# uC.net
KiCad netlist of a schematic drawn in Altium Designer
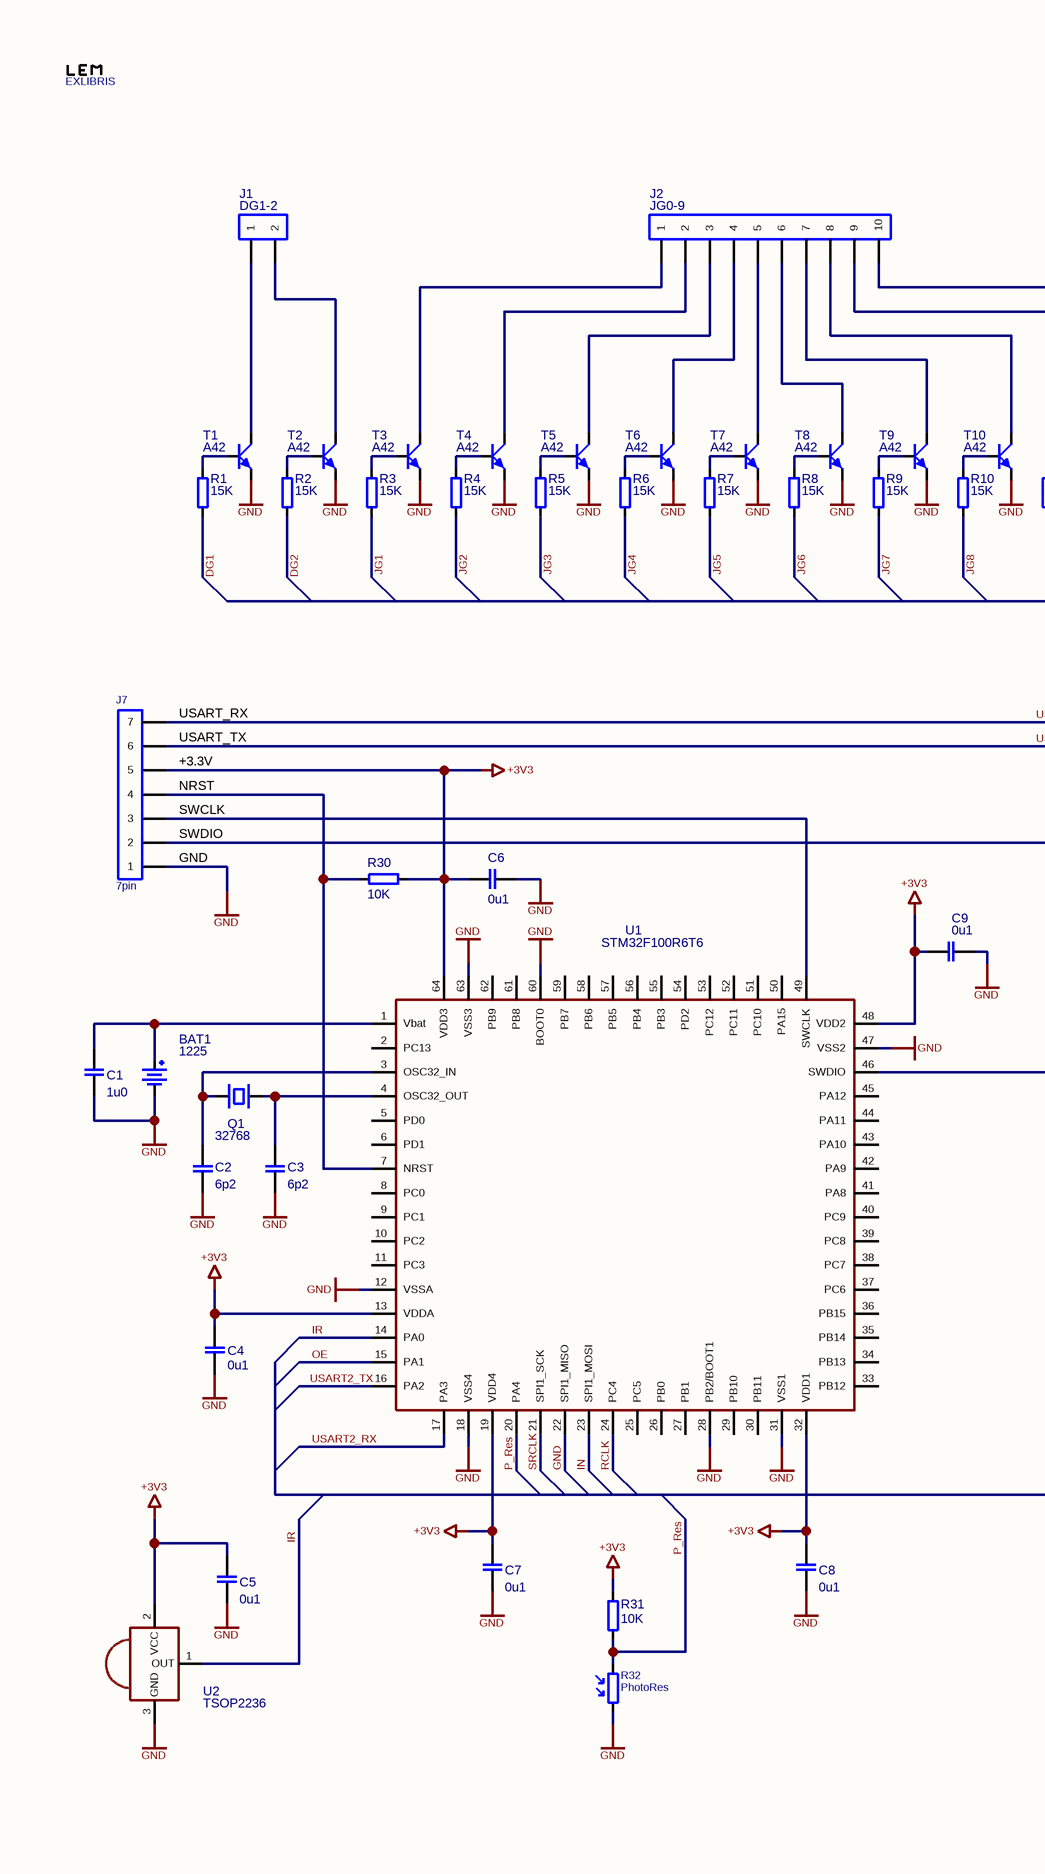
[diagram p0: uC.SchDoc, left]
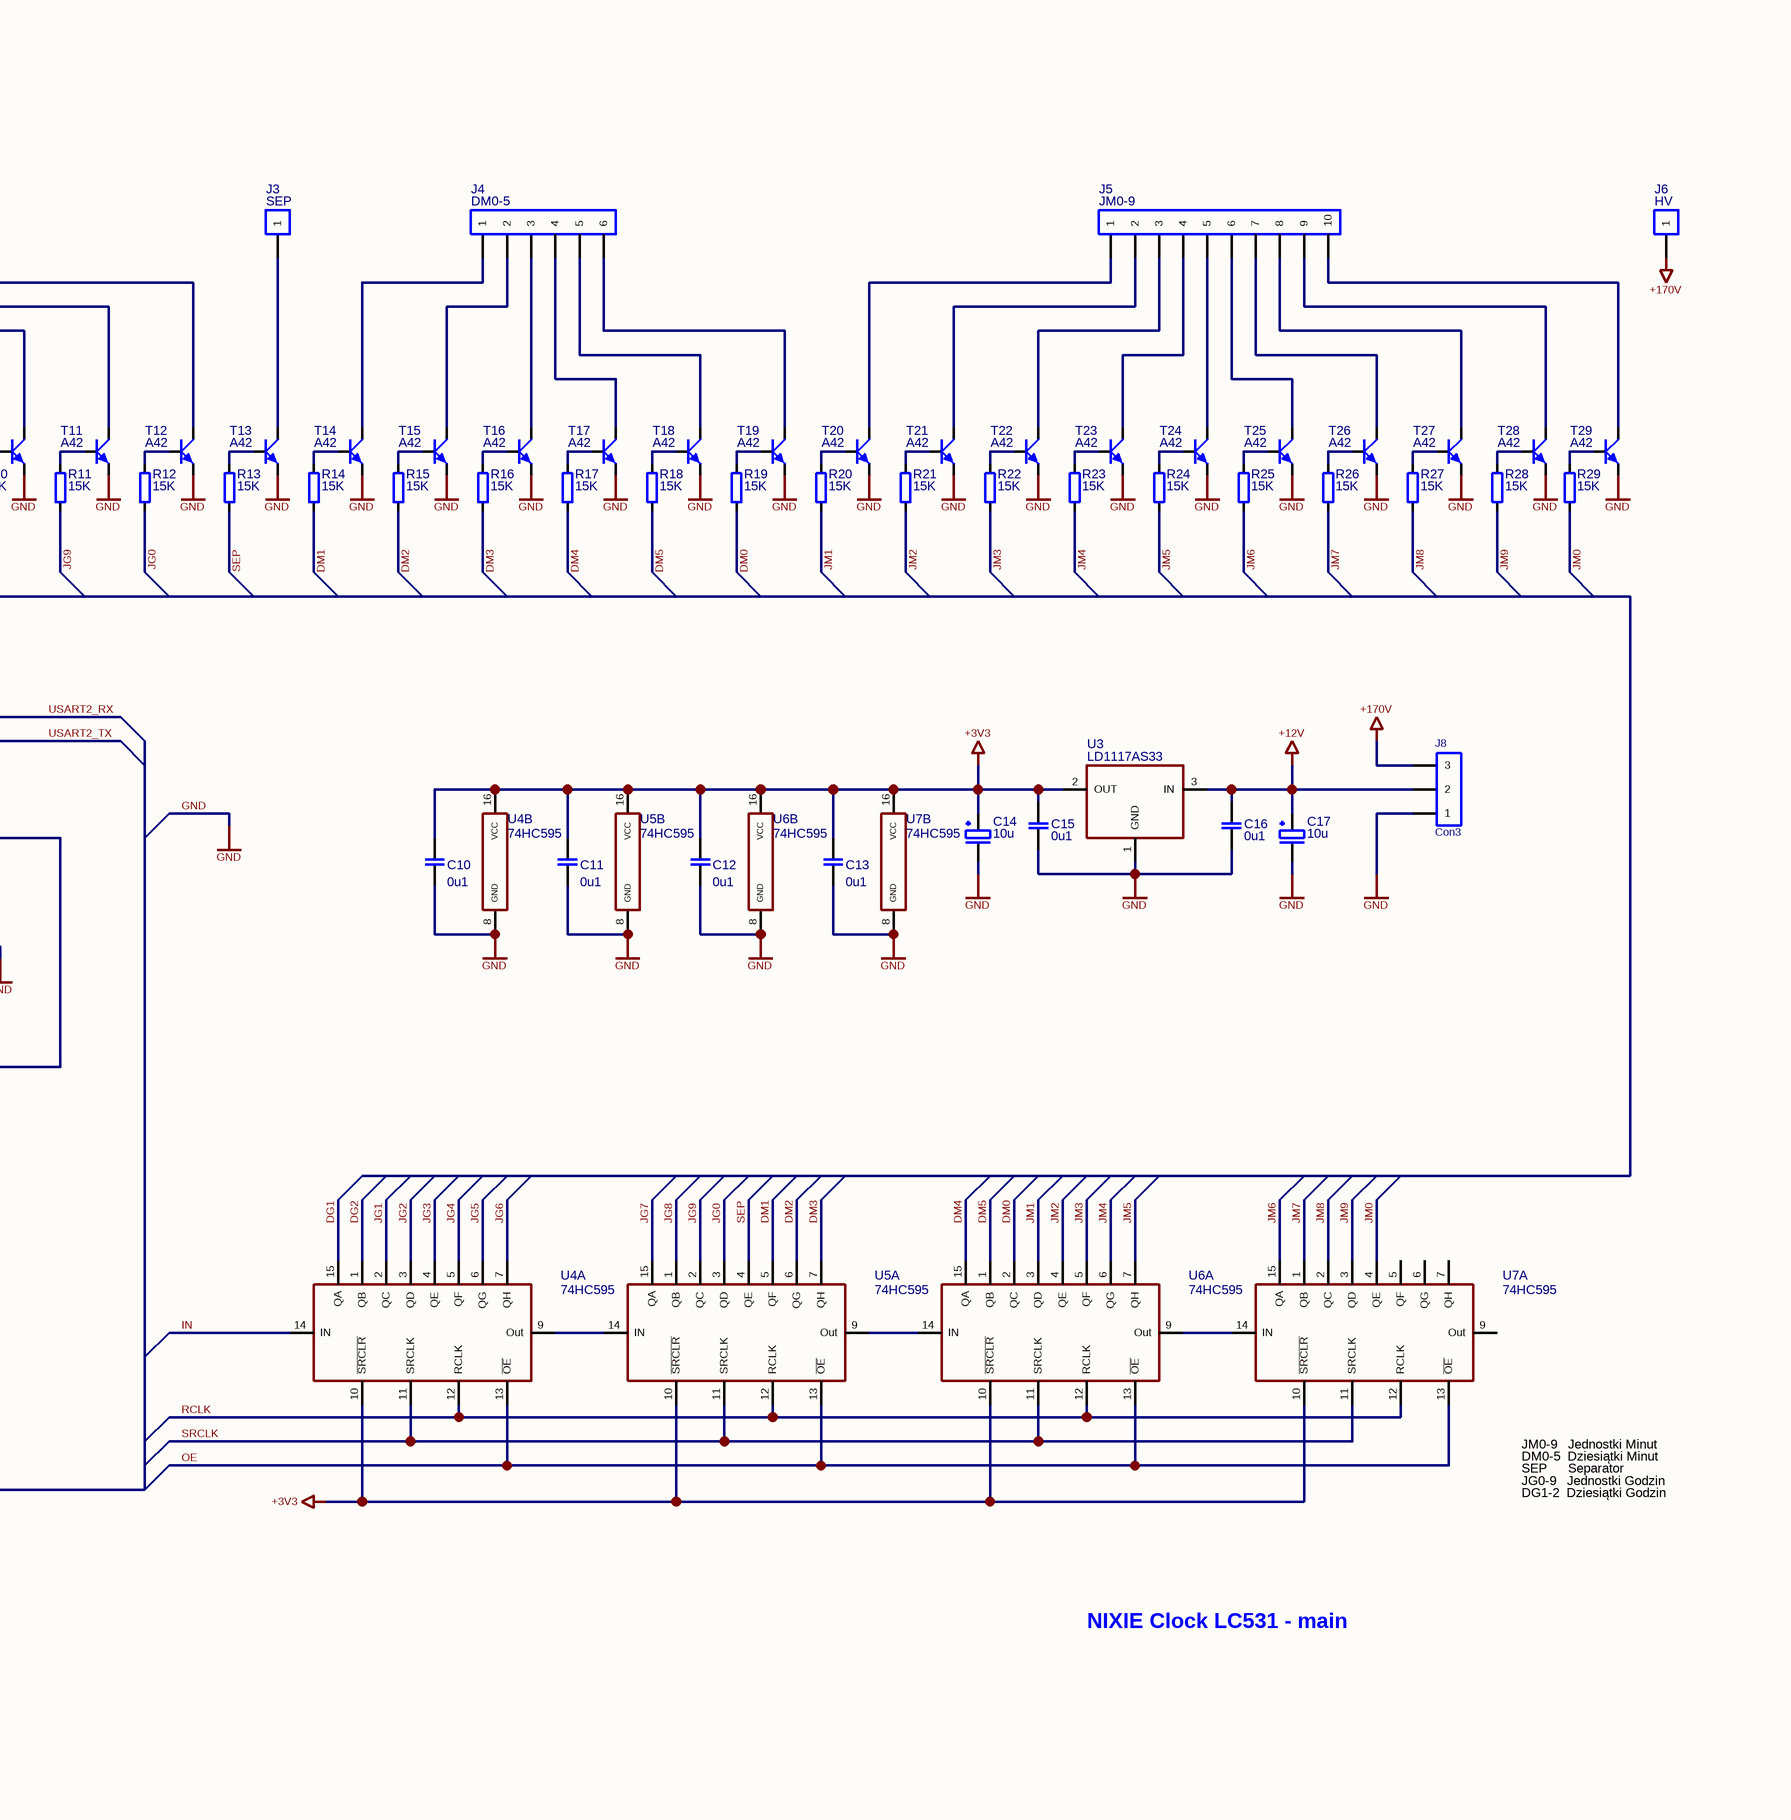
[diagram p1: uC.SchDoc, right]

(export (version "E")
  (design (tool "Eeschema 10.0.6"))
  (components
    (comp (ref "BAT1")
      (value "1225")
      (footprint "SMTU-1225")
      (description "Bateria Litowa 3V")
      (libsource (lib "Sch_Passive") (part "BAT_3V"))
    )
    (comp (ref "C1")
      (value "1u0")
      (footprint "C_SMD_0805")
      (description "Kondensator monolityczny")
      (libsource (lib "Caps") (part "C"))
    )
    (comp (ref "C2")
      (value "6p2")
      (footprint "C_SMD_0805")
      (description "Kondensator monolityczny")
      (libsource (lib "Caps") (part "C"))
    )
    (comp (ref "C3")
      (value "6p2")
      (footprint "C_SMD_0805")
      (description "Kondensator monolityczny")
      (libsource (lib "Caps") (part "C"))
    )
    (comp (ref "C4")
      (value "0u1")
      (footprint "C_SMD_0603")
      (description "Kondensator monolityczny")
      (libsource (lib "Caps") (part "C"))
    )
    (comp (ref "C5")
      (value "0u1")
      (footprint "C_SMD_0603")
      (description "Kondensator monolityczny")
      (libsource (lib "Caps") (part "C"))
    )
    (comp (ref "C6")
      (value "0u1")
      (footprint "C_SMD_0603")
      (description "Kondensator monolityczny")
      (libsource (lib "Caps") (part "C"))
    )
    (comp (ref "C7")
      (value "0u1")
      (footprint "C_SMD_0603")
      (description "Kondensator monolityczny")
      (libsource (lib "Caps") (part "C"))
    )
    (comp (ref "C8")
      (value "0u1")
      (footprint "C_SMD_0603")
      (description "Kondensator monolityczny")
      (libsource (lib "Caps") (part "C"))
    )
    (comp (ref "C9")
      (value "0u1")
      (footprint "C_SMD_0603")
      (description "Kondensator monolityczny")
      (libsource (lib "Caps") (part "C"))
    )
    (comp (ref "C10")
      (value "0u1")
      (footprint "C_SMD_0603")
      (description "Kondensator monolityczny")
      (libsource (lib "Caps") (part "C"))
    )
    (comp (ref "C11")
      (value "0u1")
      (footprint "C_SMD_0603")
      (description "Kondensator monolityczny")
      (libsource (lib "Caps") (part "C"))
    )
    (comp (ref "C12")
      (value "0u1")
      (footprint "C_SMD_0603")
      (description "Kondensator monolityczny")
      (libsource (lib "Caps") (part "C"))
    )
    (comp (ref "C13")
      (value "0u1")
      (footprint "C_SMD_0603")
      (description "Kondensator monolityczny")
      (libsource (lib "Caps") (part "C"))
    )
    (comp (ref "C14")
      (value "10u")
      (footprint "CE_T_SMC_6032_28")
      (description "Kondensator elektrolityczny")
      (libsource (lib "Caps") (part "CE"))
    )
    (comp (ref "C15")
      (value "0u1")
      (footprint "C_SMD_0603")
      (description "Kondensator monolityczny")
      (libsource (lib "Caps") (part "C"))
    )
    (comp (ref "C16")
      (value "0u1")
      (footprint "C_SMD_0603")
      (description "Kondensator monolityczny")
      (libsource (lib "Caps") (part "C"))
    )
    (comp (ref "C17")
      (value "10u")
      (footprint "CE_T_SMC_6032_28")
      (description "Kondensator elektrolityczny")
      (libsource (lib "Caps") (part "CE"))
    )
    (comp (ref "EXLIBRIS") (value "EXLIBRIS") (footprint "EXLBS_2") (libsource (lib "Misc") (part "EXLBR")))
    (comp (ref "J1")
      (value "DG1-2")
      (footprint "SIL2_GP_V")
      (description "Connector 2pin")
      (libsource (lib "Connectors") (part "CON 2pin"))
    )
    (comp (ref "J2")
      (value "JG0-9")
      (footprint "SIL10")
      (description "Connector 10 pin")
      (libsource (lib "Connectors") (part "CON 10pin"))
    )
    (comp (ref "J3")
      (value "SEP")
      (footprint "SIL1")
      (description "Connector 1pin also mounting hole")
      (libsource (lib "Connectors") (part "CON 1pin"))
    )
    (comp (ref "J4")
      (value "DM0-5")
      (footprint "SIL6_GP_V")
      (description "6 Pin Connector")
      (libsource (lib "Connectors") (part "CON 6pin"))
    )
    (comp (ref "J5")
      (value "JM0-9")
      (footprint "SIL10")
      (description "Connector 10 pin")
      (libsource (lib "Connectors") (part "CON 10pin"))
    )
    (comp (ref "J6")
      (value "HV")
      (footprint "SIL1")
      (description "Connector 1pin also mounting hole")
      (libsource (lib "Connectors") (part "CON 1pin"))
    )
    (comp (ref "J7")
      (value "7pin")
      (footprint "SIL7_SMD_Horizontal")
      (description "Connector 7pin")
      (libsource (lib "Connectors") (part "CON 7pin"))
    )
    (comp (ref "J8")
      (value "Con3")
      (footprint "TE_147323-2")
      (description "Connector 3pin")
      (libsource (lib "Connectors") (part "CON 3pin"))
    )
    (comp (ref "Q1")
      (value "32768")
      (footprint "XTAL_3")
      (description "Rezonator kwarcowy")
      (libsource (lib "Sch_Passive") (part "Q"))
    )
    (comp (ref "R1")
      (value "15K")
      (footprint "R_SMD_0603")
      (description "Resistor")
      (libsource (lib "Res") (part "R"))
    )
    (comp (ref "R2")
      (value "15K")
      (footprint "R_SMD_0603")
      (description "Resistor")
      (libsource (lib "Res") (part "R"))
    )
    (comp (ref "R3")
      (value "15K")
      (footprint "R_SMD_0603")
      (description "Resistor")
      (libsource (lib "Res") (part "R"))
    )
    (comp (ref "R4")
      (value "15K")
      (footprint "R_SMD_0603")
      (description "Resistor")
      (libsource (lib "Res") (part "R"))
    )
    (comp (ref "R5")
      (value "15K")
      (footprint "R_SMD_0603")
      (description "Resistor")
      (libsource (lib "Res") (part "R"))
    )
    (comp (ref "R6")
      (value "15K")
      (footprint "R_SMD_0603")
      (description "Resistor")
      (libsource (lib "Res") (part "R"))
    )
    (comp (ref "R7")
      (value "15K")
      (footprint "R_SMD_0603")
      (description "Resistor")
      (libsource (lib "Res") (part "R"))
    )
    (comp (ref "R8")
      (value "15K")
      (footprint "R_SMD_0603")
      (description "Resistor")
      (libsource (lib "Res") (part "R"))
    )
    (comp (ref "R9")
      (value "15K")
      (footprint "R_SMD_0603")
      (description "Resistor")
      (libsource (lib "Res") (part "R"))
    )
    (comp (ref "R10")
      (value "15K")
      (footprint "R_SMD_0603")
      (description "Resistor")
      (libsource (lib "Res") (part "R"))
    )
    (comp (ref "R11")
      (value "15K")
      (footprint "R_SMD_0603")
      (description "Resistor")
      (libsource (lib "Res") (part "R"))
    )
    (comp (ref "R12")
      (value "15K")
      (footprint "R_SMD_0603")
      (description "Resistor")
      (libsource (lib "Res") (part "R"))
    )
    (comp (ref "R13")
      (value "15K")
      (footprint "R_SMD_0603")
      (description "Resistor")
      (libsource (lib "Res") (part "R"))
    )
    (comp (ref "R14")
      (value "15K")
      (footprint "R_SMD_0603")
      (description "Resistor")
      (libsource (lib "Res") (part "R"))
    )
    (comp (ref "R15")
      (value "15K")
      (footprint "R_SMD_0603")
      (description "Resistor")
      (libsource (lib "Res") (part "R"))
    )
    (comp (ref "R16")
      (value "15K")
      (footprint "R_SMD_0603")
      (description "Resistor")
      (libsource (lib "Res") (part "R"))
    )
    (comp (ref "R17")
      (value "15K")
      (footprint "R_SMD_0603")
      (description "Resistor")
      (libsource (lib "Res") (part "R"))
    )
    (comp (ref "R18")
      (value "15K")
      (footprint "R_SMD_0603")
      (description "Resistor")
      (libsource (lib "Res") (part "R"))
    )
    (comp (ref "R19")
      (value "15K")
      (footprint "R_SMD_0603")
      (description "Resistor")
      (libsource (lib "Res") (part "R"))
    )
    (comp (ref "R20")
      (value "15K")
      (footprint "R_SMD_0603")
      (description "Resistor")
      (libsource (lib "Res") (part "R"))
    )
    (comp (ref "R21")
      (value "15K")
      (footprint "R_SMD_0603")
      (description "Resistor")
      (libsource (lib "Res") (part "R"))
    )
    (comp (ref "R22")
      (value "15K")
      (footprint "R_SMD_0603")
      (description "Resistor")
      (libsource (lib "Res") (part "R"))
    )
    (comp (ref "R23")
      (value "15K")
      (footprint "R_SMD_0603")
      (description "Resistor")
      (libsource (lib "Res") (part "R"))
    )
    (comp (ref "R24")
      (value "15K")
      (footprint "R_SMD_0603")
      (description "Resistor")
      (libsource (lib "Res") (part "R"))
    )
    (comp (ref "R25")
      (value "15K")
      (footprint "R_SMD_0603")
      (description "Resistor")
      (libsource (lib "Res") (part "R"))
    )
    (comp (ref "R26")
      (value "15K")
      (footprint "R_SMD_0603")
      (description "Resistor")
      (libsource (lib "Res") (part "R"))
    )
    (comp (ref "R27")
      (value "15K")
      (footprint "R_SMD_0603")
      (description "Resistor")
      (libsource (lib "Res") (part "R"))
    )
    (comp (ref "R28")
      (value "15K")
      (footprint "R_SMD_0603")
      (description "Resistor")
      (libsource (lib "Res") (part "R"))
    )
    (comp (ref "R29")
      (value "15K")
      (footprint "R_SMD_0603")
      (description "Resistor")
      (libsource (lib "Res") (part "R"))
    )
    (comp (ref "R30")
      (value "10K")
      (footprint "R_SMD_0603")
      (description "Resistor")
      (libsource (lib "Res") (part "R"))
    )
    (comp (ref "R31")
      (value "10K")
      (footprint "R_SMD_0603")
      (description "Resistor")
      (libsource (lib "Res") (part "R"))
    )
    (comp (ref "R32")
      (value "PhotoRes")
      (footprint "R_Photo_V")
      (description "Photo resistor")
      (libsource (lib "RLCDQ") (part "R_Ph"))
    )
    (comp (ref "T1")
      (value "A42")
      (footprint "SOT-23 - Basic")
      (description "High Voltage NPN transistor")
      (libsource (lib "Tranzystory") (part "MMBTA42"))
    )
    (comp (ref "T2")
      (value "A42")
      (footprint "SOT-23 - Basic")
      (description "High Voltage NPN transistor")
      (libsource (lib "Tranzystory") (part "MMBTA42"))
    )
    (comp (ref "T3")
      (value "A42")
      (footprint "SOT-23 - Basic")
      (description "High Voltage NPN transistor")
      (libsource (lib "Tranzystory") (part "MMBTA42"))
    )
    (comp (ref "T4")
      (value "A42")
      (footprint "SOT-23 - Basic")
      (description "High Voltage NPN transistor")
      (libsource (lib "Tranzystory") (part "MMBTA42"))
    )
    (comp (ref "T5")
      (value "A42")
      (footprint "SOT-23 - Basic")
      (description "High Voltage NPN transistor")
      (libsource (lib "Tranzystory") (part "MMBTA42"))
    )
    (comp (ref "T6")
      (value "A42")
      (footprint "SOT-23 - Basic")
      (description "High Voltage NPN transistor")
      (libsource (lib "Tranzystory") (part "MMBTA42"))
    )
    (comp (ref "T7")
      (value "A42")
      (footprint "SOT-23 - Basic")
      (description "High Voltage NPN transistor")
      (libsource (lib "Tranzystory") (part "MMBTA42"))
    )
    (comp (ref "T8")
      (value "A42")
      (footprint "SOT-23 - Basic")
      (description "High Voltage NPN transistor")
      (libsource (lib "Tranzystory") (part "MMBTA42"))
    )
    (comp (ref "T9")
      (value "A42")
      (footprint "SOT-23 - Basic")
      (description "High Voltage NPN transistor")
      (libsource (lib "Tranzystory") (part "MMBTA42"))
    )
    (comp (ref "T10")
      (value "A42")
      (footprint "SOT-23 - Basic")
      (description "High Voltage NPN transistor")
      (libsource (lib "Tranzystory") (part "MMBTA42"))
    )
    (comp (ref "T11")
      (value "A42")
      (footprint "SOT-23 - Basic")
      (description "High Voltage NPN transistor")
      (libsource (lib "Tranzystory") (part "MMBTA42"))
    )
    (comp (ref "T12")
      (value "A42")
      (footprint "SOT-23 - Basic")
      (description "High Voltage NPN transistor")
      (libsource (lib "Tranzystory") (part "MMBTA42"))
    )
    (comp (ref "T13")
      (value "A42")
      (footprint "SOT-23 - Basic")
      (description "High Voltage NPN transistor")
      (libsource (lib "Tranzystory") (part "MMBTA42"))
    )
    (comp (ref "T14")
      (value "A42")
      (footprint "SOT-23 - Basic")
      (description "High Voltage NPN transistor")
      (libsource (lib "Tranzystory") (part "MMBTA42"))
    )
    (comp (ref "T15")
      (value "A42")
      (footprint "SOT-23 - Basic")
      (description "High Voltage NPN transistor")
      (libsource (lib "Tranzystory") (part "MMBTA42"))
    )
    (comp (ref "T16")
      (value "A42")
      (footprint "SOT-23 - Basic")
      (description "High Voltage NPN transistor")
      (libsource (lib "Tranzystory") (part "MMBTA42"))
    )
    (comp (ref "T17")
      (value "A42")
      (footprint "SOT-23 - Basic")
      (description "High Voltage NPN transistor")
      (libsource (lib "Tranzystory") (part "MMBTA42"))
    )
    (comp (ref "T18")
      (value "A42")
      (footprint "SOT-23 - Basic")
      (description "High Voltage NPN transistor")
      (libsource (lib "Tranzystory") (part "MMBTA42"))
    )
    (comp (ref "T19")
      (value "A42")
      (footprint "SOT-23 - Basic")
      (description "High Voltage NPN transistor")
      (libsource (lib "Tranzystory") (part "MMBTA42"))
    )
    (comp (ref "T20")
      (value "A42")
      (footprint "SOT-23 - Basic")
      (description "High Voltage NPN transistor")
      (libsource (lib "Tranzystory") (part "MMBTA42"))
    )
    (comp (ref "T21")
      (value "A42")
      (footprint "SOT-23 - Basic")
      (description "High Voltage NPN transistor")
      (libsource (lib "Tranzystory") (part "MMBTA42"))
    )
    (comp (ref "T22")
      (value "A42")
      (footprint "SOT-23 - Basic")
      (description "High Voltage NPN transistor")
      (libsource (lib "Tranzystory") (part "MMBTA42"))
    )
    (comp (ref "T23")
      (value "A42")
      (footprint "SOT-23 - Basic")
      (description "High Voltage NPN transistor")
      (libsource (lib "Tranzystory") (part "MMBTA42"))
    )
    (comp (ref "T24")
      (value "A42")
      (footprint "SOT-23 - Basic")
      (description "High Voltage NPN transistor")
      (libsource (lib "Tranzystory") (part "MMBTA42"))
    )
    (comp (ref "T25")
      (value "A42")
      (footprint "SOT-23 - Basic")
      (description "High Voltage NPN transistor")
      (libsource (lib "Tranzystory") (part "MMBTA42"))
    )
    (comp (ref "T26")
      (value "A42")
      (footprint "SOT-23 - Basic")
      (description "High Voltage NPN transistor")
      (libsource (lib "Tranzystory") (part "MMBTA42"))
    )
    (comp (ref "T27")
      (value "A42")
      (footprint "SOT-23 - Basic")
      (description "High Voltage NPN transistor")
      (libsource (lib "Tranzystory") (part "MMBTA42"))
    )
    (comp (ref "T28")
      (value "A42")
      (footprint "SOT-23 - Basic")
      (description "High Voltage NPN transistor")
      (libsource (lib "Tranzystory") (part "MMBTA42"))
    )
    (comp (ref "T29")
      (value "A42")
      (footprint "SOT-23 - Basic")
      (description "High Voltage NPN transistor")
      (libsource (lib "Tranzystory") (part "MMBTA42"))
    )
    (comp (ref "U1")
      (value "STM32F100R6T6")
      (footprint "LQFP-674")
      (libsource (lib "uC") (part "STM32F100R6T6"))
    )
    (comp (ref "U2") (value "TSOP2236") (footprint "TSOP-2236") (libsource (lib "uC") (part "IR Reciver")))
    (comp (ref "U3") (value "LD1117AS33") (footprint "SOT-223") (libsource (lib "uC") (part "AMS1117_3V3")))
    (comp (ref "U4")
      (value "74HC595")
      (footprint "SO-16_150")
      (description "8-bit shift registers with 3-state output")
      (libsource (lib "uC") (part "74595"))
    )
    (comp (ref "U5")
      (value "74HC595")
      (footprint "SO-16_150")
      (description "8-bit shift registers with 3-state output")
      (libsource (lib "uC") (part "74595"))
    )
    (comp (ref "U6")
      (value "74HC595")
      (footprint "SO-16_150")
      (description "8-bit shift registers with 3-state output")
      (libsource (lib "uC") (part "74595"))
    )
    (comp (ref "U7")
      (value "74HC595")
      (footprint "SO-16_150")
      (description "8-bit shift registers with 3-state output")
      (libsource (lib "uC") (part "74595"))
    )
  )
  (nets
    (net (code "1") (name "+3V3") (class "Default")
      (node (ref "C10") (pin "2") (pinfunction "2_2") (pintype "passive"))
      (node (ref "C11") (pin "2") (pinfunction "2_2") (pintype "passive"))
      (node (ref "C12") (pin "2") (pinfunction "2_2") (pintype "passive"))
      (node (ref "C13") (pin "2") (pinfunction "2_2") (pintype "passive"))
      (node (ref "C14") (pin "2") (pinfunction "+_2") (pintype "passive"))
      (node (ref "C15") (pin "2") (pinfunction "2_2") (pintype "passive"))
      (node (ref "C4") (pin "1") (pinfunction "1_1") (pintype "passive"))
      (node (ref "C5") (pin "2") (pinfunction "2_2") (pintype "passive"))
      (node (ref "C6") (pin "2") (pinfunction "2_2") (pintype "passive"))
      (node (ref "C7") (pin "2") (pinfunction "2_2") (pintype "passive"))
      (node (ref "C8") (pin "2") (pinfunction "2_2") (pintype "passive"))
      (node (ref "C9") (pin "1") (pinfunction "1_1") (pintype "passive"))
      (node (ref "J7") (pin "5") (pinfunction "5_5") (pintype "passive"))
      (node (ref "R30") (pin "1") (pinfunction "1_1") (pintype "passive"))
      (node (ref "R31") (pin "1") (pinfunction "1_1") (pintype "passive"))
      (node (ref "U1") (pin "13") (pinfunction "VDDA_13") (pintype "passive"))
      (node (ref "U1") (pin "19") (pinfunction "VDD4_19") (pintype "passive"))
      (node (ref "U1") (pin "32") (pinfunction "VDD1_32") (pintype "passive"))
      (node (ref "U1") (pin "48") (pinfunction "VDD2_48") (pintype "passive"))
      (node (ref "U1") (pin "64") (pinfunction "VDD3_64") (pintype "passive"))
      (node (ref "U2") (pin "2") (pinfunction "VCC_2") (pintype "passive"))
      (node (ref "U3") (pin "2") (pinfunction "OUT_2") (pintype "passive"))
      (node (ref "U4") (pin "10") (pinfunction "~{SRCLR}_10") (pintype "passive"))
      (node (ref "U4") (pin "16") (pinfunction "VCC_16") (pintype "passive"))
      (node (ref "U5") (pin "10") (pinfunction "~{SRCLR}_10") (pintype "passive"))
      (node (ref "U5") (pin "16") (pinfunction "VCC_16") (pintype "passive"))
      (node (ref "U6") (pin "10") (pinfunction "~{SRCLR}_10") (pintype "passive"))
      (node (ref "U6") (pin "16") (pinfunction "VCC_16") (pintype "passive"))
      (node (ref "U7") (pin "10") (pinfunction "~{SRCLR}_10") (pintype "passive"))
      (node (ref "U7") (pin "16") (pinfunction "VCC_16") (pintype "passive"))
    )
    (net (code "2") (name "+12V") (class "Default")
      (node (ref "C16") (pin "2") (pinfunction "2_2") (pintype "passive"))
      (node (ref "C17") (pin "2") (pinfunction "+_2") (pintype "passive"))
      (node (ref "J8") (pin "2") (pinfunction "2_2") (pintype "passive"))
      (node (ref "U3") (pin "3") (pinfunction "IN_3") (pintype "passive"))
    )
    (net (code "3") (name "+170V") (class "Default")
      (node (ref "J6") (pin "1") (pinfunction "1_1") (pintype "passive"))
      (node (ref "J8") (pin "3") (pinfunction "3_3") (pintype "passive"))
    )
    (net (code "4") (name "/DG1") (class "Default")
      (node (ref "R1") (pin "1") (pinfunction "1_1") (pintype "passive"))
      (node (ref "U4") (pin "15") (pinfunction "QA_15") (pintype "passive"))
    )
    (net (code "5") (name "/DG2") (class "Default")
      (node (ref "R2") (pin "1") (pinfunction "1_1") (pintype "passive"))
      (node (ref "U4") (pin "1") (pinfunction "QB_1") (pintype "passive"))
    )
    (net (code "6") (name "/DM0") (class "Default")
      (node (ref "R19") (pin "1") (pinfunction "1_1") (pintype "passive"))
      (node (ref "U6") (pin "2") (pinfunction "QC_2") (pintype "passive"))
    )
    (net (code "7") (name "/DM1") (class "Default")
      (node (ref "R14") (pin "1") (pinfunction "1_1") (pintype "passive"))
      (node (ref "U5") (pin "5") (pinfunction "QF_5") (pintype "passive"))
    )
    (net (code "8") (name "/DM2") (class "Default")
      (node (ref "R15") (pin "1") (pinfunction "1_1") (pintype "passive"))
      (node (ref "U5") (pin "6") (pinfunction "QG_6") (pintype "passive"))
    )
    (net (code "9") (name "/DM3") (class "Default")
      (node (ref "R16") (pin "1") (pinfunction "1_1") (pintype "passive"))
      (node (ref "U5") (pin "7") (pinfunction "QH_7") (pintype "passive"))
    )
    (net (code "10") (name "/DM4") (class "Default")
      (node (ref "R17") (pin "1") (pinfunction "1_1") (pintype "passive"))
      (node (ref "U6") (pin "15") (pinfunction "QA_15") (pintype "passive"))
    )
    (net (code "11") (name "/DM5") (class "Default")
      (node (ref "R18") (pin "2") (pinfunction "2_2") (pintype "passive"))
      (node (ref "U6") (pin "1") (pinfunction "QB_1") (pintype "passive"))
    )
    (net (code "12") (name "/IN") (class "Default")
      (node (ref "U1") (pin "23") (pinfunction "SPI1_MOSI_23") (pintype "passive"))
      (node (ref "U4") (pin "14") (pinfunction "IN_14") (pintype "passive"))
    )
    (net (code "13") (name "/IR") (class "Default")
      (node (ref "U1") (pin "14") (pinfunction "PA0_14") (pintype "passive"))
      (node (ref "U2") (pin "1") (pinfunction "OUT_1") (pintype "passive"))
    )
    (net (code "14") (name "/JG0") (class "Default")
      (node (ref "R12") (pin "1") (pinfunction "1_1") (pintype "passive"))
      (node (ref "U5") (pin "3") (pinfunction "QD_3") (pintype "passive"))
    )
    (net (code "15") (name "/JG1") (class "Default")
      (node (ref "R3") (pin "2") (pinfunction "2_2") (pintype "passive"))
      (node (ref "U4") (pin "2") (pinfunction "QC_2") (pintype "passive"))
    )
    (net (code "16") (name "/JG2") (class "Default")
      (node (ref "R4") (pin "1") (pinfunction "1_1") (pintype "passive"))
      (node (ref "U4") (pin "3") (pinfunction "QD_3") (pintype "passive"))
    )
    (net (code "17") (name "/JG3") (class "Default")
      (node (ref "R5") (pin "1") (pinfunction "1_1") (pintype "passive"))
      (node (ref "U4") (pin "4") (pinfunction "QE_4") (pintype "passive"))
    )
    (net (code "18") (name "/JG4") (class "Default")
      (node (ref "R6") (pin "1") (pinfunction "1_1") (pintype "passive"))
      (node (ref "U4") (pin "5") (pinfunction "QF_5") (pintype "passive"))
    )
    (net (code "19") (name "/JG5") (class "Default")
      (node (ref "R7") (pin "1") (pinfunction "1_1") (pintype "passive"))
      (node (ref "U4") (pin "6") (pinfunction "QG_6") (pintype "passive"))
    )
    (net (code "20") (name "/JG6") (class "Default")
      (node (ref "R8") (pin "2") (pinfunction "2_2") (pintype "passive"))
      (node (ref "U4") (pin "7") (pinfunction "QH_7") (pintype "passive"))
    )
    (net (code "21") (name "/JG7") (class "Default")
      (node (ref "R9") (pin "1") (pinfunction "1_1") (pintype "passive"))
      (node (ref "U5") (pin "15") (pinfunction "QA_15") (pintype "passive"))
    )
    (net (code "22") (name "/JG8") (class "Default")
      (node (ref "R10") (pin "1") (pinfunction "1_1") (pintype "passive"))
      (node (ref "U5") (pin "1") (pinfunction "QB_1") (pintype "passive"))
    )
    (net (code "23") (name "/JG9") (class "Default")
      (node (ref "R11") (pin "1") (pinfunction "1_1") (pintype "passive"))
      (node (ref "U5") (pin "2") (pinfunction "QC_2") (pintype "passive"))
    )
    (net (code "24") (name "/JM0") (class "Default")
      (node (ref "R29") (pin "1") (pinfunction "1_1") (pintype "passive"))
      (node (ref "U7") (pin "4") (pinfunction "QE_4") (pintype "passive"))
    )
    (net (code "25") (name "/JM1") (class "Default")
      (node (ref "R20") (pin "1") (pinfunction "1_1") (pintype "passive"))
      (node (ref "U6") (pin "3") (pinfunction "QD_3") (pintype "passive"))
    )
    (net (code "26") (name "/JM2") (class "Default")
      (node (ref "R21") (pin "1") (pinfunction "1_1") (pintype "passive"))
      (node (ref "U6") (pin "4") (pinfunction "QE_4") (pintype "passive"))
    )
    (net (code "27") (name "/JM3") (class "Default")
      (node (ref "R22") (pin "1") (pinfunction "1_1") (pintype "passive"))
      (node (ref "U6") (pin "5") (pinfunction "QF_5") (pintype "passive"))
    )
    (net (code "28") (name "/JM4") (class "Default")
      (node (ref "R23") (pin "2") (pinfunction "2_2") (pintype "passive"))
      (node (ref "U6") (pin "6") (pinfunction "QG_6") (pintype "passive"))
    )
    (net (code "29") (name "/JM5") (class "Default")
      (node (ref "R24") (pin "1") (pinfunction "1_1") (pintype "passive"))
      (node (ref "U6") (pin "7") (pinfunction "QH_7") (pintype "passive"))
    )
    (net (code "30") (name "/JM6") (class "Default")
      (node (ref "R25") (pin "1") (pinfunction "1_1") (pintype "passive"))
      (node (ref "U7") (pin "15") (pinfunction "QA_15") (pintype "passive"))
    )
    (net (code "31") (name "/JM7") (class "Default")
      (node (ref "R26") (pin "1") (pinfunction "1_1") (pintype "passive"))
      (node (ref "U7") (pin "1") (pinfunction "QB_1") (pintype "passive"))
    )
    (net (code "32") (name "/JM8") (class "Default")
      (node (ref "R27") (pin "1") (pinfunction "1_1") (pintype "passive"))
      (node (ref "U7") (pin "2") (pinfunction "QC_2") (pintype "passive"))
    )
    (net (code "33") (name "/JM9") (class "Default")
      (node (ref "R28") (pin "2") (pinfunction "2_2") (pintype "passive"))
      (node (ref "U7") (pin "3") (pinfunction "QD_3") (pintype "passive"))
    )
    (net (code "34") (name "/OE") (class "Default")
      (node (ref "U1") (pin "15") (pinfunction "PA1_15") (pintype "passive"))
      (node (ref "U4") (pin "13") (pinfunction "~{OE}_13") (pintype "passive"))
      (node (ref "U5") (pin "13") (pinfunction "~{OE}_13") (pintype "passive"))
      (node (ref "U6") (pin "13") (pinfunction "~{OE}_13") (pintype "passive"))
      (node (ref "U7") (pin "13") (pinfunction "~{OE}_13") (pintype "passive"))
    )
    (net (code "35") (name "/P_Res") (class "Default")
      (node (ref "R31") (pin "2") (pinfunction "2_2") (pintype "passive"))
      (node (ref "R32") (pin "2") (pinfunction "+_2") (pintype "passive"))
      (node (ref "U1") (pin "20") (pinfunction "PA4_20") (pintype "passive"))
    )
    (net (code "36") (name "/RCLK") (class "Default")
      (node (ref "U1") (pin "24") (pinfunction "PC4_24") (pintype "passive"))
      (node (ref "U4") (pin "12") (pinfunction "RCLK_12") (pintype "passive"))
      (node (ref "U5") (pin "12") (pinfunction "RCLK_12") (pintype "passive"))
      (node (ref "U6") (pin "12") (pinfunction "RCLK_12") (pintype "passive"))
      (node (ref "U7") (pin "12") (pinfunction "RCLK_12") (pintype "passive"))
    )
    (net (code "37") (name "/SEP") (class "Default")
      (node (ref "R13") (pin "2") (pinfunction "2_2") (pintype "passive"))
      (node (ref "U5") (pin "4") (pinfunction "QE_4") (pintype "passive"))
    )
    (net (code "38") (name "/SRCLK") (class "Default")
      (node (ref "U1") (pin "21") (pinfunction "SPI1_SCK_21") (pintype "passive"))
      (node (ref "U4") (pin "11") (pinfunction "SRCLK_11") (pintype "passive"))
      (node (ref "U5") (pin "11") (pinfunction "SRCLK_11") (pintype "passive"))
      (node (ref "U6") (pin "11") (pinfunction "SRCLK_11") (pintype "passive"))
      (node (ref "U7") (pin "11") (pinfunction "SRCLK_11") (pintype "passive"))
    )
    (net (code "39") (name "/USART2_RX") (class "Default")
      (node (ref "J7") (pin "7") (pinfunction "7_7") (pintype "passive"))
      (node (ref "U1") (pin "17") (pinfunction "PA3_17") (pintype "passive"))
    )
    (net (code "40") (name "/USART2_TX") (class "Default")
      (node (ref "J7") (pin "6") (pinfunction "6_6") (pintype "passive"))
      (node (ref "U1") (pin "16") (pinfunction "PA2_16") (pintype "passive"))
    )
    (net (code "41") (name "GND") (class "Default")
      (node (ref "BAT1") (pin "2") (pinfunction "-_2") (pintype "passive"))
      (node (ref "C1") (pin "1") (pinfunction "1_1") (pintype "passive"))
      (node (ref "C10") (pin "1") (pinfunction "1_1") (pintype "passive"))
      (node (ref "C11") (pin "1") (pinfunction "1_1") (pintype "passive"))
      (node (ref "C12") (pin "1") (pinfunction "1_1") (pintype "passive"))
      (node (ref "C13") (pin "1") (pinfunction "1_1") (pintype "passive"))
      (node (ref "C14") (pin "1") (pinfunction "-_1") (pintype "passive"))
      (node (ref "C15") (pin "1") (pinfunction "1_1") (pintype "passive"))
      (node (ref "C16") (pin "1") (pinfunction "1_1") (pintype "passive"))
      (node (ref "C17") (pin "1") (pinfunction "-_1") (pintype "passive"))
      (node (ref "C2") (pin "1") (pinfunction "1_1") (pintype "passive"))
      (node (ref "C3") (pin "1") (pinfunction "1_1") (pintype "passive"))
      (node (ref "C4") (pin "2") (pinfunction "2_2") (pintype "passive"))
      (node (ref "C5") (pin "1") (pinfunction "1_1") (pintype "passive"))
      (node (ref "C6") (pin "1") (pinfunction "1_1") (pintype "passive"))
      (node (ref "C7") (pin "1") (pinfunction "1_1") (pintype "passive"))
      (node (ref "C8") (pin "1") (pinfunction "1_1") (pintype "passive"))
      (node (ref "C9") (pin "2") (pinfunction "2_2") (pintype "passive"))
      (node (ref "J7") (pin "1") (pinfunction "1_1") (pintype "passive"))
      (node (ref "J8") (pin "1") (pinfunction "1_1") (pintype "passive"))
      (node (ref "R32") (pin "1") (pinfunction "-_1") (pintype "passive"))
      (node (ref "T1") (pin "2") (pinfunction "Emitter_2") (pintype "passive"))
      (node (ref "T10") (pin "2") (pinfunction "Emitter_2") (pintype "passive"))
      (node (ref "T11") (pin "2") (pinfunction "Emitter_2") (pintype "passive"))
      (node (ref "T12") (pin "2") (pinfunction "Emitter_2") (pintype "passive"))
      (node (ref "T13") (pin "2") (pinfunction "Emitter_2") (pintype "passive"))
      (node (ref "T14") (pin "2") (pinfunction "Emitter_2") (pintype "passive"))
      (node (ref "T15") (pin "2") (pinfunction "Emitter_2") (pintype "passive"))
      (node (ref "T16") (pin "2") (pinfunction "Emitter_2") (pintype "passive"))
      (node (ref "T17") (pin "2") (pinfunction "Emitter_2") (pintype "passive"))
      (node (ref "T18") (pin "2") (pinfunction "Emitter_2") (pintype "passive"))
      (node (ref "T19") (pin "2") (pinfunction "Emitter_2") (pintype "passive"))
      (node (ref "T2") (pin "2") (pinfunction "Emitter_2") (pintype "passive"))
      (node (ref "T20") (pin "2") (pinfunction "Emitter_2") (pintype "passive"))
      (node (ref "T21") (pin "2") (pinfunction "Emitter_2") (pintype "passive"))
      (node (ref "T22") (pin "2") (pinfunction "Emitter_2") (pintype "passive"))
      (node (ref "T23") (pin "2") (pinfunction "Emitter_2") (pintype "passive"))
      (node (ref "T24") (pin "2") (pinfunction "Emitter_2") (pintype "passive"))
      (node (ref "T25") (pin "2") (pinfunction "Emitter_2") (pintype "passive"))
      (node (ref "T26") (pin "2") (pinfunction "Emitter_2") (pintype "passive"))
      (node (ref "T27") (pin "2") (pinfunction "Emitter_2") (pintype "passive"))
      (node (ref "T28") (pin "2") (pinfunction "Emitter_2") (pintype "passive"))
      (node (ref "T29") (pin "2") (pinfunction "Emitter_2") (pintype "passive"))
      (node (ref "T3") (pin "2") (pinfunction "Emitter_2") (pintype "passive"))
      (node (ref "T4") (pin "2") (pinfunction "Emitter_2") (pintype "passive"))
      (node (ref "T5") (pin "2") (pinfunction "Emitter_2") (pintype "passive"))
      (node (ref "T6") (pin "2") (pinfunction "Emitter_2") (pintype "passive"))
      (node (ref "T7") (pin "2") (pinfunction "Emitter_2") (pintype "passive"))
      (node (ref "T8") (pin "2") (pinfunction "Emitter_2") (pintype "passive"))
      (node (ref "T9") (pin "2") (pinfunction "Emitter_2") (pintype "passive"))
      (node (ref "U1") (pin "12") (pinfunction "VSSA_12") (pintype "passive"))
      (node (ref "U1") (pin "18") (pinfunction "VSS4_18") (pintype "passive"))
      (node (ref "U1") (pin "22") (pinfunction "SPI1_MISO_22") (pintype "passive"))
      (node (ref "U1") (pin "28") (pinfunction "PB2/BOOT1_28") (pintype "passive"))
      (node (ref "U1") (pin "31") (pinfunction "VSS1_31") (pintype "passive"))
      (node (ref "U1") (pin "47") (pinfunction "VSS2_47") (pintype "passive"))
      (node (ref "U1") (pin "60") (pinfunction "BOOT0_60") (pintype "passive"))
      (node (ref "U1") (pin "63") (pinfunction "VSS3_63") (pintype "passive"))
      (node (ref "U2") (pin "3") (pinfunction "GND_3") (pintype "passive"))
      (node (ref "U3") (pin "1") (pinfunction "GND_1") (pintype "passive"))
      (node (ref "U4") (pin "8") (pinfunction "GND_8") (pintype "power_in"))
      (node (ref "U5") (pin "8") (pinfunction "GND_8") (pintype "power_in"))
      (node (ref "U6") (pin "8") (pinfunction "GND_8") (pintype "power_in"))
      (node (ref "U7") (pin "8") (pinfunction "GND_8") (pintype "power_in"))
    )
    (net (code "42") (name "Net-(BAT1-+)") (class "Default")
      (node (ref "BAT1") (pin "1") (pinfunction "+_1") (pintype "passive"))
      (node (ref "C1") (pin "2") (pinfunction "2_2") (pintype "passive"))
      (node (ref "U1") (pin "1") (pinfunction "Vbat_1") (pintype "passive"))
    )
    (net (code "43") (name "Net-(T1-Base)") (class "Default")
      (node (ref "R1") (pin "2") (pinfunction "2_2") (pintype "passive"))
      (node (ref "T1") (pin "1") (pinfunction "Base_1") (pintype "passive"))
    )
    (net (code "44") (name "Net-(T1-Collector)") (class "Default")
      (node (ref "J1") (pin "1") (pinfunction "1_1") (pintype "passive"))
      (node (ref "T1") (pin "3") (pinfunction "Collector_3") (pintype "passive"))
    )
    (net (code "45") (name "Net-(T2-Base)") (class "Default")
      (node (ref "R2") (pin "2") (pinfunction "2_2") (pintype "passive"))
      (node (ref "T2") (pin "1") (pinfunction "Base_1") (pintype "passive"))
    )
    (net (code "46") (name "Net-(T2-Collector)") (class "Default")
      (node (ref "J1") (pin "2") (pinfunction "2_2") (pintype "passive"))
      (node (ref "T2") (pin "3") (pinfunction "Collector_3") (pintype "passive"))
    )
    (net (code "47") (name "Net-(T3-Base)") (class "Default")
      (node (ref "R3") (pin "1") (pinfunction "1_1") (pintype "passive"))
      (node (ref "T3") (pin "1") (pinfunction "Base_1") (pintype "passive"))
    )
    (net (code "48") (name "Net-(T3-Collector)") (class "Default")
      (node (ref "J2") (pin "1") (pinfunction "1_1") (pintype "passive"))
      (node (ref "T3") (pin "3") (pinfunction "Collector_3") (pintype "passive"))
    )
    (net (code "49") (name "Net-(T4-Base)") (class "Default")
      (node (ref "R4") (pin "2") (pinfunction "2_2") (pintype "passive"))
      (node (ref "T4") (pin "1") (pinfunction "Base_1") (pintype "passive"))
    )
    (net (code "50") (name "Net-(T4-Collector)") (class "Default")
      (node (ref "J2") (pin "2") (pinfunction "2_2") (pintype "passive"))
      (node (ref "T4") (pin "3") (pinfunction "Collector_3") (pintype "passive"))
    )
    (net (code "51") (name "Net-(T5-Base)") (class "Default")
      (node (ref "R5") (pin "2") (pinfunction "2_2") (pintype "passive"))
      (node (ref "T5") (pin "1") (pinfunction "Base_1") (pintype "passive"))
    )
    (net (code "52") (name "Net-(T5-Collector)") (class "Default")
      (node (ref "J2") (pin "3") (pinfunction "3_3") (pintype "passive"))
      (node (ref "T5") (pin "3") (pinfunction "Collector_3") (pintype "passive"))
    )
    (net (code "53") (name "Net-(T6-Base)") (class "Default")
      (node (ref "R6") (pin "2") (pinfunction "2_2") (pintype "passive"))
      (node (ref "T6") (pin "1") (pinfunction "Base_1") (pintype "passive"))
    )
    (net (code "54") (name "Net-(T6-Collector)") (class "Default")
      (node (ref "J2") (pin "4") (pinfunction "4_4") (pintype "passive"))
      (node (ref "T6") (pin "3") (pinfunction "Collector_3") (pintype "passive"))
    )
    (net (code "55") (name "Net-(T7-Base)") (class "Default")
      (node (ref "R7") (pin "2") (pinfunction "2_2") (pintype "passive"))
      (node (ref "T7") (pin "1") (pinfunction "Base_1") (pintype "passive"))
    )
    (net (code "56") (name "Net-(T7-Collector)") (class "Default")
      (node (ref "J2") (pin "5") (pinfunction "5_5") (pintype "passive"))
      (node (ref "T7") (pin "3") (pinfunction "Collector_3") (pintype "passive"))
    )
    (net (code "57") (name "Net-(T8-Base)") (class "Default")
      (node (ref "R8") (pin "1") (pinfunction "1_1") (pintype "passive"))
      (node (ref "T8") (pin "1") (pinfunction "Base_1") (pintype "passive"))
    )
    (net (code "58") (name "Net-(T8-Collector)") (class "Default")
      (node (ref "J2") (pin "6") (pinfunction "6_6") (pintype "passive"))
      (node (ref "T8") (pin "3") (pinfunction "Collector_3") (pintype "passive"))
    )
    (net (code "59") (name "Net-(T9-Base)") (class "Default")
      (node (ref "R9") (pin "2") (pinfunction "2_2") (pintype "passive"))
      (node (ref "T9") (pin "1") (pinfunction "Base_1") (pintype "passive"))
    )
    (net (code "60") (name "Net-(T9-Collector)") (class "Default")
      (node (ref "J2") (pin "7") (pinfunction "7_7") (pintype "passive"))
      (node (ref "T9") (pin "3") (pinfunction "Collector_3") (pintype "passive"))
    )
    (net (code "61") (name "Net-(T10-Base)") (class "Default")
      (node (ref "R10") (pin "2") (pinfunction "2_2") (pintype "passive"))
      (node (ref "T10") (pin "1") (pinfunction "Base_1") (pintype "passive"))
    )
    (net (code "62") (name "Net-(T10-Collector)") (class "Default")
      (node (ref "J2") (pin "8") (pinfunction "8_8") (pintype "passive"))
      (node (ref "T10") (pin "3") (pinfunction "Collector_3") (pintype "passive"))
    )
    (net (code "63") (name "Net-(T11-Base)") (class "Default")
      (node (ref "R11") (pin "2") (pinfunction "2_2") (pintype "passive"))
      (node (ref "T11") (pin "1") (pinfunction "Base_1") (pintype "passive"))
    )
    (net (code "64") (name "Net-(T11-Collector)") (class "Default")
      (node (ref "J2") (pin "9") (pinfunction "9_9") (pintype "passive"))
      (node (ref "T11") (pin "3") (pinfunction "Collector_3") (pintype "passive"))
    )
    (net (code "65") (name "Net-(T12-Base)") (class "Default")
      (node (ref "R12") (pin "2") (pinfunction "2_2") (pintype "passive"))
      (node (ref "T12") (pin "1") (pinfunction "Base_1") (pintype "passive"))
    )
    (net (code "66") (name "Net-(T12-Collector)") (class "Default")
      (node (ref "J2") (pin "10") (pinfunction "10_10") (pintype "passive"))
      (node (ref "T12") (pin "3") (pinfunction "Collector_3") (pintype "passive"))
    )
    (net (code "67") (name "Net-(T13-Base)") (class "Default")
      (node (ref "R13") (pin "1") (pinfunction "1_1") (pintype "passive"))
      (node (ref "T13") (pin "1") (pinfunction "Base_1") (pintype "passive"))
    )
    (net (code "68") (name "Net-(T13-Collector)") (class "Default")
      (node (ref "J3") (pin "1") (pinfunction "1_1") (pintype "passive"))
      (node (ref "T13") (pin "3") (pinfunction "Collector_3") (pintype "passive"))
    )
    (net (code "69") (name "Net-(T14-Base)") (class "Default")
      (node (ref "R14") (pin "2") (pinfunction "2_2") (pintype "passive"))
      (node (ref "T14") (pin "1") (pinfunction "Base_1") (pintype "passive"))
    )
    (net (code "70") (name "Net-(T14-Collector)") (class "Default")
      (node (ref "J4") (pin "1") (pinfunction "1_1") (pintype "passive"))
      (node (ref "T14") (pin "3") (pinfunction "Collector_3") (pintype "passive"))
    )
    (net (code "71") (name "Net-(T15-Base)") (class "Default")
      (node (ref "R15") (pin "2") (pinfunction "2_2") (pintype "passive"))
      (node (ref "T15") (pin "1") (pinfunction "Base_1") (pintype "passive"))
    )
    (net (code "72") (name "Net-(T15-Collector)") (class "Default")
      (node (ref "J4") (pin "2") (pinfunction "2_2") (pintype "passive"))
      (node (ref "T15") (pin "3") (pinfunction "Collector_3") (pintype "passive"))
    )
    (net (code "73") (name "Net-(T16-Base)") (class "Default")
      (node (ref "R16") (pin "2") (pinfunction "2_2") (pintype "passive"))
      (node (ref "T16") (pin "1") (pinfunction "Base_1") (pintype "passive"))
    )
    (net (code "74") (name "Net-(T16-Collector)") (class "Default")
      (node (ref "J4") (pin "3") (pinfunction "3_3") (pintype "passive"))
      (node (ref "T16") (pin "3") (pinfunction "Collector_3") (pintype "passive"))
    )
    (net (code "75") (name "Net-(T17-Base)") (class "Default")
      (node (ref "R17") (pin "2") (pinfunction "2_2") (pintype "passive"))
      (node (ref "T17") (pin "1") (pinfunction "Base_1") (pintype "passive"))
    )
    (net (code "76") (name "Net-(T17-Collector)") (class "Default")
      (node (ref "J4") (pin "4") (pinfunction "4_4") (pintype "passive"))
      (node (ref "T17") (pin "3") (pinfunction "Collector_3") (pintype "passive"))
    )
    (net (code "77") (name "Net-(T18-Base)") (class "Default")
      (node (ref "R18") (pin "1") (pinfunction "1_1") (pintype "passive"))
      (node (ref "T18") (pin "1") (pinfunction "Base_1") (pintype "passive"))
    )
    (net (code "78") (name "Net-(T18-Collector)") (class "Default")
      (node (ref "J4") (pin "5") (pinfunction "5_5") (pintype "passive"))
      (node (ref "T18") (pin "3") (pinfunction "Collector_3") (pintype "passive"))
    )
    (net (code "79") (name "Net-(T19-Base)") (class "Default")
      (node (ref "R19") (pin "2") (pinfunction "2_2") (pintype "passive"))
      (node (ref "T19") (pin "1") (pinfunction "Base_1") (pintype "passive"))
    )
    (net (code "80") (name "Net-(T19-Collector)") (class "Default")
      (node (ref "J4") (pin "6") (pinfunction "6_6") (pintype "passive"))
      (node (ref "T19") (pin "3") (pinfunction "Collector_3") (pintype "passive"))
    )
    (net (code "81") (name "Net-(T20-Base)") (class "Default")
      (node (ref "R20") (pin "2") (pinfunction "2_2") (pintype "passive"))
      (node (ref "T20") (pin "1") (pinfunction "Base_1") (pintype "passive"))
    )
    (net (code "82") (name "Net-(T20-Collector)") (class "Default")
      (node (ref "J5") (pin "1") (pinfunction "1_1") (pintype "passive"))
      (node (ref "T20") (pin "3") (pinfunction "Collector_3") (pintype "passive"))
    )
    (net (code "83") (name "Net-(T21-Base)") (class "Default")
      (node (ref "R21") (pin "2") (pinfunction "2_2") (pintype "passive"))
      (node (ref "T21") (pin "1") (pinfunction "Base_1") (pintype "passive"))
    )
    (net (code "84") (name "Net-(T21-Collector)") (class "Default")
      (node (ref "J5") (pin "2") (pinfunction "2_2") (pintype "passive"))
      (node (ref "T21") (pin "3") (pinfunction "Collector_3") (pintype "passive"))
    )
    (net (code "85") (name "Net-(T22-Base)") (class "Default")
      (node (ref "R22") (pin "2") (pinfunction "2_2") (pintype "passive"))
      (node (ref "T22") (pin "1") (pinfunction "Base_1") (pintype "passive"))
    )
    (net (code "86") (name "Net-(T22-Collector)") (class "Default")
      (node (ref "J5") (pin "3") (pinfunction "3_3") (pintype "passive"))
      (node (ref "T22") (pin "3") (pinfunction "Collector_3") (pintype "passive"))
    )
    (net (code "87") (name "Net-(T23-Base)") (class "Default")
      (node (ref "R23") (pin "1") (pinfunction "1_1") (pintype "passive"))
      (node (ref "T23") (pin "1") (pinfunction "Base_1") (pintype "passive"))
    )
    (net (code "88") (name "Net-(T23-Collector)") (class "Default")
      (node (ref "J5") (pin "4") (pinfunction "4_4") (pintype "passive"))
      (node (ref "T23") (pin "3") (pinfunction "Collector_3") (pintype "passive"))
    )
    (net (code "89") (name "Net-(T24-Base)") (class "Default")
      (node (ref "R24") (pin "2") (pinfunction "2_2") (pintype "passive"))
      (node (ref "T24") (pin "1") (pinfunction "Base_1") (pintype "passive"))
    )
    (net (code "90") (name "Net-(T24-Collector)") (class "Default")
      (node (ref "J5") (pin "5") (pinfunction "5_5") (pintype "passive"))
      (node (ref "T24") (pin "3") (pinfunction "Collector_3") (pintype "passive"))
    )
    (net (code "91") (name "Net-(T25-Base)") (class "Default")
      (node (ref "R25") (pin "2") (pinfunction "2_2") (pintype "passive"))
      (node (ref "T25") (pin "1") (pinfunction "Base_1") (pintype "passive"))
    )
    (net (code "92") (name "Net-(T25-Collector)") (class "Default")
      (node (ref "J5") (pin "6") (pinfunction "6_6") (pintype "passive"))
      (node (ref "T25") (pin "3") (pinfunction "Collector_3") (pintype "passive"))
    )
    (net (code "93") (name "Net-(T26-Base)") (class "Default")
      (node (ref "R26") (pin "2") (pinfunction "2_2") (pintype "passive"))
      (node (ref "T26") (pin "1") (pinfunction "Base_1") (pintype "passive"))
    )
    (net (code "94") (name "Net-(T26-Collector)") (class "Default")
      (node (ref "J5") (pin "7") (pinfunction "7_7") (pintype "passive"))
      (node (ref "T26") (pin "3") (pinfunction "Collector_3") (pintype "passive"))
    )
    (net (code "95") (name "Net-(T27-Base)") (class "Default")
      (node (ref "R27") (pin "2") (pinfunction "2_2") (pintype "passive"))
      (node (ref "T27") (pin "1") (pinfunction "Base_1") (pintype "passive"))
    )
    (net (code "96") (name "Net-(T27-Collector)") (class "Default")
      (node (ref "J5") (pin "8") (pinfunction "8_8") (pintype "passive"))
      (node (ref "T27") (pin "3") (pinfunction "Collector_3") (pintype "passive"))
    )
    (net (code "97") (name "Net-(T28-Base)") (class "Default")
      (node (ref "R28") (pin "1") (pinfunction "1_1") (pintype "passive"))
      (node (ref "T28") (pin "1") (pinfunction "Base_1") (pintype "passive"))
    )
    (net (code "98") (name "Net-(T28-Collector)") (class "Default")
      (node (ref "J5") (pin "9") (pinfunction "9_9") (pintype "passive"))
      (node (ref "T28") (pin "3") (pinfunction "Collector_3") (pintype "passive"))
    )
    (net (code "99") (name "Net-(T29-Base)") (class "Default")
      (node (ref "R29") (pin "2") (pinfunction "2_2") (pintype "passive"))
      (node (ref "T29") (pin "1") (pinfunction "Base_1") (pintype "passive"))
    )
    (net (code "100") (name "Net-(T29-Collector)") (class "Default")
      (node (ref "J5") (pin "10") (pinfunction "10_10") (pintype "passive"))
      (node (ref "T29") (pin "3") (pinfunction "Collector_3") (pintype "passive"))
    )
    (net (code "101") (name "Net-(U1-NRST)") (class "Default")
      (node (ref "J7") (pin "4") (pinfunction "4_4") (pintype "passive"))
      (node (ref "R30") (pin "2") (pinfunction "2_2") (pintype "passive"))
      (node (ref "U1") (pin "7") (pinfunction "NRST_7") (pintype "passive"))
    )
    (net (code "102") (name "Net-(U1-OSC32_IN)") (class "Default")
      (node (ref "C2") (pin "2") (pinfunction "2_2") (pintype "passive"))
      (node (ref "Q1") (pin "1") (pinfunction "1_1") (pintype "passive"))
      (node (ref "U1") (pin "3") (pinfunction "OSC32_IN_3") (pintype "passive"))
    )
    (net (code "103") (name "Net-(U1-OSC32_OUT)") (class "Default")
      (node (ref "C3") (pin "2") (pinfunction "2_2") (pintype "passive"))
      (node (ref "Q1") (pin "2") (pinfunction "2_2") (pintype "passive"))
      (node (ref "U1") (pin "4") (pinfunction "OSC32_OUT_4") (pintype "passive"))
    )
    (net (code "104") (name "Net-(U1-SWCLK)") (class "Default")
      (node (ref "J7") (pin "3") (pinfunction "3_3") (pintype "passive"))
      (node (ref "U1") (pin "49") (pinfunction "SWCLK_49") (pintype "passive"))
    )
    (net (code "105") (name "Net-(U1-SWDIO)") (class "Default")
      (node (ref "J7") (pin "2") (pinfunction "2_2") (pintype "passive"))
      (node (ref "U1") (pin "46") (pinfunction "SWDIO_46") (pintype "passive"))
    )
    (net (code "106") (name "Net-(U4A-Out)") (class "Default")
      (node (ref "U4") (pin "9") (pinfunction "Out_9") (pintype "passive"))
      (node (ref "U5") (pin "14") (pinfunction "IN_14") (pintype "passive"))
    )
    (net (code "107") (name "Net-(U5A-Out)") (class "Default")
      (node (ref "U5") (pin "9") (pinfunction "Out_9") (pintype "passive"))
      (node (ref "U6") (pin "14") (pinfunction "IN_14") (pintype "passive"))
    )
    (net (code "108") (name "Net-(U6A-Out)") (class "Default")
      (node (ref "U6") (pin "9") (pinfunction "Out_9") (pintype "passive"))
      (node (ref "U7") (pin "14") (pinfunction "IN_14") (pintype "passive"))
    )
    (net (code "109") (name "unconnected-(U1-PA8-Pad41)") (class "Default")
      (node (ref "U1") (pin "41") (pinfunction "PA8_41") (pintype "passive"))
    )
    (net (code "110") (name "unconnected-(U1-PA9-Pad42)") (class "Default")
      (node (ref "U1") (pin "42") (pinfunction "PA9_42") (pintype "passive"))
    )
    (net (code "111") (name "unconnected-(U1-PA10-Pad43)") (class "Default")
      (node (ref "U1") (pin "43") (pinfunction "PA10_43") (pintype "passive"))
    )
    (net (code "112") (name "unconnected-(U1-PA11-Pad44)") (class "Default")
      (node (ref "U1") (pin "44") (pinfunction "PA11_44") (pintype "passive"))
    )
    (net (code "113") (name "unconnected-(U1-PA12-Pad45)") (class "Default")
      (node (ref "U1") (pin "45") (pinfunction "PA12_45") (pintype "passive"))
    )
    (net (code "114") (name "unconnected-(U1-PA15-Pad50)") (class "Default")
      (node (ref "U1") (pin "50") (pinfunction "PA15_50") (pintype "passive"))
    )
    (net (code "115") (name "unconnected-(U1-PB0-Pad26)") (class "Default")
      (node (ref "U1") (pin "26") (pinfunction "PB0_26") (pintype "passive"))
    )
    (net (code "116") (name "unconnected-(U1-PB1-Pad27)") (class "Default")
      (node (ref "U1") (pin "27") (pinfunction "PB1_27") (pintype "passive"))
    )
    (net (code "117") (name "unconnected-(U1-PB3-Pad55)") (class "Default")
      (node (ref "U1") (pin "55") (pinfunction "PB3_55") (pintype "passive"))
    )
    (net (code "118") (name "unconnected-(U1-PB4-Pad56)") (class "Default")
      (node (ref "U1") (pin "56") (pinfunction "PB4_56") (pintype "passive"))
    )
    (net (code "119") (name "unconnected-(U1-PB5-Pad57)") (class "Default")
      (node (ref "U1") (pin "57") (pinfunction "PB5_57") (pintype "passive"))
    )
    (net (code "120") (name "unconnected-(U1-PB6-Pad58)") (class "Default")
      (node (ref "U1") (pin "58") (pinfunction "PB6_58") (pintype "passive"))
    )
    (net (code "121") (name "unconnected-(U1-PB7-Pad59)") (class "Default")
      (node (ref "U1") (pin "59") (pinfunction "PB7_59") (pintype "passive"))
    )
    (net (code "122") (name "unconnected-(U1-PB8-Pad61)") (class "Default")
      (node (ref "U1") (pin "61") (pinfunction "PB8_61") (pintype "passive"))
    )
    (net (code "123") (name "unconnected-(U1-PB9-Pad62)") (class "Default")
      (node (ref "U1") (pin "62") (pinfunction "PB9_62") (pintype "passive"))
    )
    (net (code "124") (name "unconnected-(U1-PB10-Pad29)") (class "Default")
      (node (ref "U1") (pin "29") (pinfunction "PB10_29") (pintype "passive"))
    )
    (net (code "125") (name "unconnected-(U1-PB11-Pad30)") (class "Default")
      (node (ref "U1") (pin "30") (pinfunction "PB11_30") (pintype "passive"))
    )
    (net (code "126") (name "unconnected-(U1-PB12-Pad33)") (class "Default")
      (node (ref "U1") (pin "33") (pinfunction "PB12_33") (pintype "passive"))
    )
    (net (code "127") (name "unconnected-(U1-PB13-Pad34)") (class "Default")
      (node (ref "U1") (pin "34") (pinfunction "PB13_34") (pintype "passive"))
    )
    (net (code "128") (name "unconnected-(U1-PB14-Pad35)") (class "Default")
      (node (ref "U1") (pin "35") (pinfunction "PB14_35") (pintype "passive"))
    )
    (net (code "129") (name "unconnected-(U1-PB15-Pad36)") (class "Default")
      (node (ref "U1") (pin "36") (pinfunction "PB15_36") (pintype "passive"))
    )
    (net (code "130") (name "unconnected-(U1-PC0-Pad8)") (class "Default")
      (node (ref "U1") (pin "8") (pinfunction "PC0_8") (pintype "passive"))
    )
    (net (code "131") (name "unconnected-(U1-PC1-Pad9)") (class "Default")
      (node (ref "U1") (pin "9") (pinfunction "PC1_9") (pintype "passive"))
    )
    (net (code "132") (name "unconnected-(U1-PC2-Pad10)") (class "Default")
      (node (ref "U1") (pin "10") (pinfunction "PC2_10") (pintype "passive"))
    )
    (net (code "133") (name "unconnected-(U1-PC3-Pad11)") (class "Default")
      (node (ref "U1") (pin "11") (pinfunction "PC3_11") (pintype "passive"))
    )
    (net (code "134") (name "unconnected-(U1-PC5-Pad25)") (class "Default")
      (node (ref "U1") (pin "25") (pinfunction "PC5_25") (pintype "passive"))
    )
    (net (code "135") (name "unconnected-(U1-PC6-Pad37)") (class "Default")
      (node (ref "U1") (pin "37") (pinfunction "PC6_37") (pintype "passive"))
    )
    (net (code "136") (name "unconnected-(U1-PC7-Pad38)") (class "Default")
      (node (ref "U1") (pin "38") (pinfunction "PC7_38") (pintype "passive"))
    )
    (net (code "137") (name "unconnected-(U1-PC8-Pad39)") (class "Default")
      (node (ref "U1") (pin "39") (pinfunction "PC8_39") (pintype "passive"))
    )
    (net (code "138") (name "unconnected-(U1-PC9-Pad40)") (class "Default")
      (node (ref "U1") (pin "40") (pinfunction "PC9_40") (pintype "passive"))
    )
    (net (code "139") (name "unconnected-(U1-PC10-Pad51)") (class "Default")
      (node (ref "U1") (pin "51") (pinfunction "PC10_51") (pintype "passive"))
    )
    (net (code "140") (name "unconnected-(U1-PC11-Pad52)") (class "Default")
      (node (ref "U1") (pin "52") (pinfunction "PC11_52") (pintype "passive"))
    )
    (net (code "141") (name "unconnected-(U1-PC12-Pad53)") (class "Default")
      (node (ref "U1") (pin "53") (pinfunction "PC12_53") (pintype "passive"))
    )
    (net (code "142") (name "unconnected-(U1-PC13-Pad2)") (class "Default")
      (node (ref "U1") (pin "2") (pinfunction "PC13_2") (pintype "passive"))
    )
    (net (code "143") (name "unconnected-(U1-PD0-Pad5)") (class "Default")
      (node (ref "U1") (pin "5") (pinfunction "PD0_5") (pintype "passive"))
    )
    (net (code "144") (name "unconnected-(U1-PD1-Pad6)") (class "Default")
      (node (ref "U1") (pin "6") (pinfunction "PD1_6") (pintype "passive"))
    )
    (net (code "145") (name "unconnected-(U1-PD2-Pad54)") (class "Default")
      (node (ref "U1") (pin "54") (pinfunction "PD2_54") (pintype "passive"))
    )
    (net (code "146") (name "unconnected-(U7A-Out-Pad9)") (class "Default")
      (node (ref "U7") (pin "9") (pinfunction "Out_9") (pintype "passive"))
    )
    (net (code "147") (name "unconnected-(U7A-QF-Pad5)") (class "Default")
      (node (ref "U7") (pin "5") (pinfunction "QF_5") (pintype "passive"))
    )
    (net (code "148") (name "unconnected-(U7A-QG-Pad6)") (class "Default")
      (node (ref "U7") (pin "6") (pinfunction "QG_6") (pintype "passive"))
    )
    (net (code "149") (name "unconnected-(U7A-QH-Pad7)") (class "Default")
      (node (ref "U7") (pin "7") (pinfunction "QH_7") (pintype "passive"))
    )
  )
)
